# 07_-_ETHERNET.net
KiCad netlist of a schematic drawn in Altium Designer
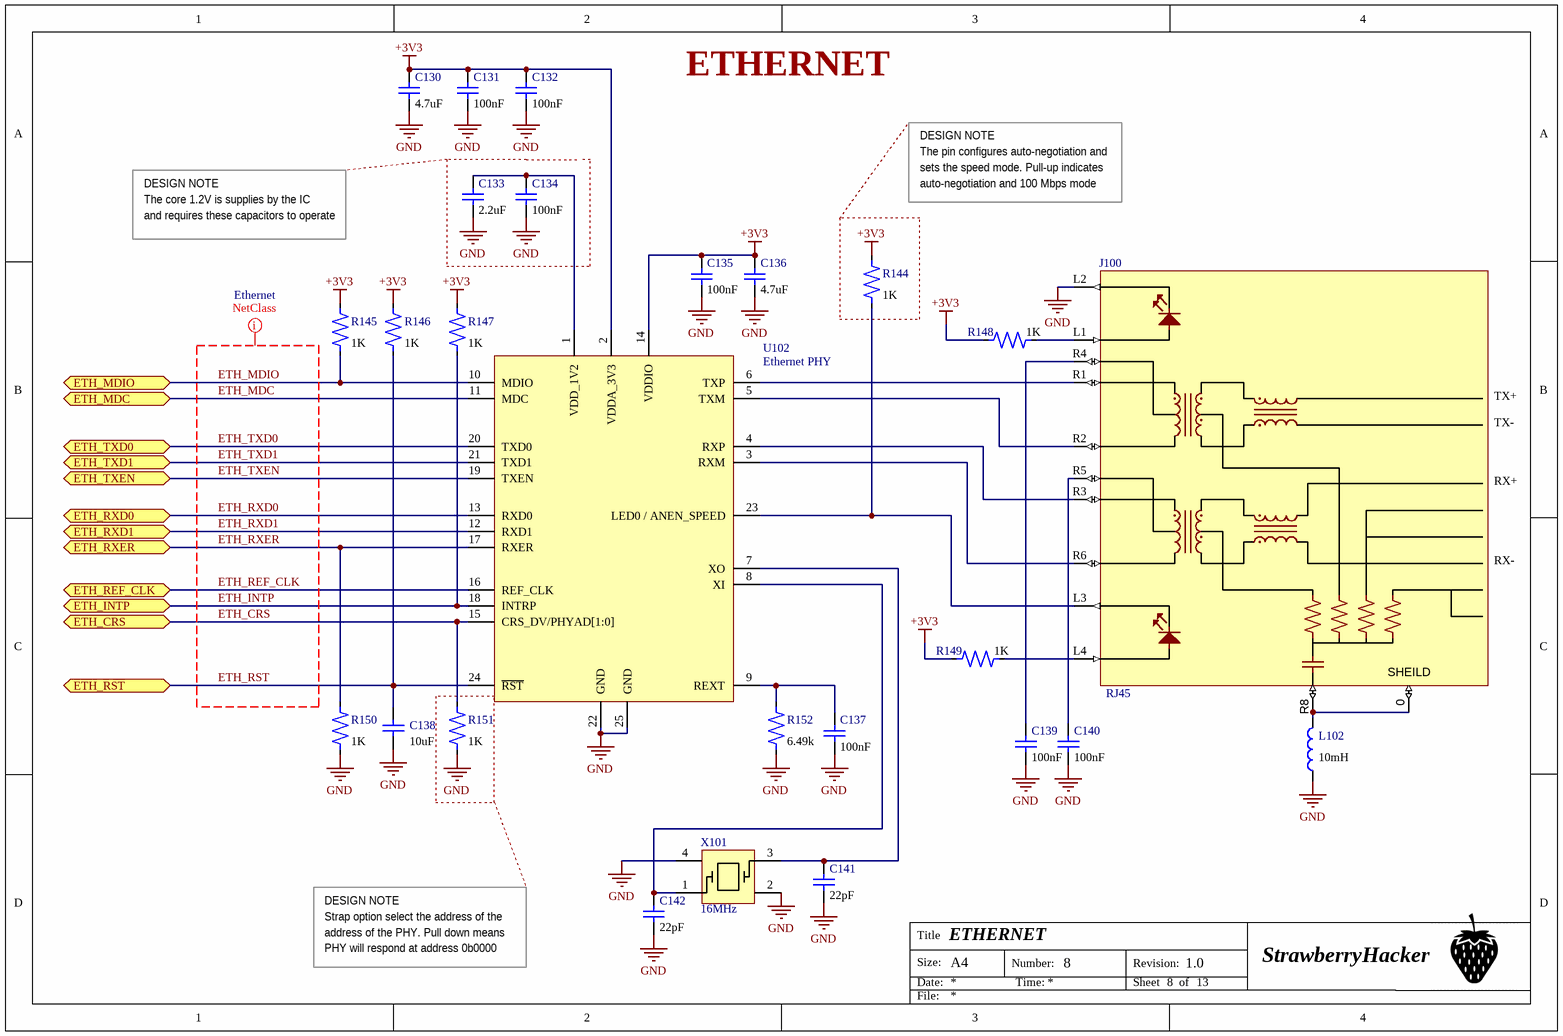
[diagram p0: [07] - ETHERNET.SchDoc]

(export (version "E")
  (design (tool "Eeschema 10.0.6"))
  (components
    (comp (ref "C130")
      (value "4.7uF")
      (footprint "C0603")
      (description "C0603")
      (fields (field (name "Comment") "02016D104KAT2A"))
      (libsource (lib "Passive components") (part "02016D104KAT2A"))
    )
    (comp (ref "C131")
      (value "100nF")
      (footprint "C0402")
      (description "C0402")
      (fields (field (name "Comment") "04023C103KAT2A"))
      (libsource (lib "Passive components") (part "04023C103KAT2A"))
    )
    (comp (ref "C132")
      (value "100nF")
      (footprint "C0402")
      (description "C0402")
      (fields (field (name "Comment") "04023C103KAT2A"))
      (libsource (lib "Passive components") (part "04023C103KAT2A"))
    )
    (comp (ref "C133")
      (value "2.2uF")
      (footprint "C0603")
      (description "C0603")
      (fields (field (name "Comment") "02016D104KAT2A"))
      (libsource (lib "Passive components") (part "02016D104KAT2A"))
    )
    (comp (ref "C134")
      (value "100nF")
      (footprint "C0402")
      (description "C0402")
      (fields (field (name "Comment") "04023C103KAT2A"))
      (libsource (lib "Passive components") (part "04023C103KAT2A"))
    )
    (comp (ref "C135")
      (value "100nF")
      (footprint "C0402")
      (description "C0402")
      (fields (field (name "Comment") "04023C103KAT2A"))
      (libsource (lib "Passive components") (part "04023C103KAT2A"))
    )
    (comp (ref "C136")
      (value "4.7uF")
      (footprint "C0603")
      (description "C0603")
      (fields (field (name "Comment") "02016D104KAT2A"))
      (libsource (lib "Passive components") (part "02016D104KAT2A"))
    )
    (comp (ref "C137")
      (value "100nF")
      (footprint "C0402")
      (description "C0402")
      (fields (field (name "Comment") "04023C103KAT2A"))
      (libsource (lib "Passive components") (part "04023C103KAT2A"))
    )
    (comp (ref "C138")
      (value "10uF")
      (footprint "C0603")
      (description "C0603")
      (fields (field (name "Comment") "02016D104KAT2A"))
      (libsource (lib "Passive components") (part "02016D104KAT2A"))
    )
    (comp (ref "C139")
      (value "100nF")
      (footprint "C0402")
      (description "C0402")
      (fields (field (name "Comment") "04023C103KAT2A"))
      (libsource (lib "Passive components") (part "04023C103KAT2A"))
    )
    (comp (ref "C140")
      (value "100nF")
      (footprint "C0402")
      (description "C0402")
      (fields (field (name "Comment") "04023C103KAT2A"))
      (libsource (lib "Passive components") (part "04023C103KAT2A"))
    )
    (comp (ref "C141")
      (value "22pF")
      (footprint "C0402")
      (description "C0402")
      (fields (field (name "Comment") "04023C103KAT2A"))
      (libsource (lib "Passive components") (part "04023C103KAT2A"))
    )
    (comp (ref "C142")
      (value "22pF")
      (footprint "C0402")
      (description "C0402")
      (fields (field (name "Comment") "04023C103KAT2A"))
      (libsource (lib "Passive components") (part "04023C103KAT2A"))
    )
    (comp (ref "J100")
      (value "RJ45")
      (footprint "RJ45 8P8C LED & magnetics")
      (description "RJ45 8P8C LED & magnetics")
      (libsource (lib "Connectors") (part "234235-2-2-1-12"))
    )
    (comp (ref "L102")
      (value "10mH")
      (footprint "Inductor 0603")
      (description "Inductor 0603")
      (fields (field (name "Comment") "MLZ1608A2R2WT"))
      (libsource (lib "Passive components") (part "MLZ1608A2R2WT"))
    )
    (comp (ref "R144")
      (value "1K")
      (footprint "R0402")
      (description "R0402")
      (fields (field (name "Comment") "CRCW04020000Z0ED"))
      (libsource (lib "Passive components") (part "CRCW04020000Z0ED"))
    )
    (comp (ref "R145")
      (value "1K")
      (footprint "R0402")
      (description "R0402")
      (fields (field (name "Comment") "CRCW04020000Z0ED"))
      (libsource (lib "Passive components") (part "CRCW04020000Z0ED"))
    )
    (comp (ref "R146")
      (value "1K")
      (footprint "R0402")
      (description "R0402")
      (fields (field (name "Comment") "CRCW04020000Z0ED"))
      (libsource (lib "Passive components") (part "CRCW04020000Z0ED"))
    )
    (comp (ref "R147")
      (value "1K")
      (footprint "R0402")
      (description "R0402")
      (fields (field (name "Comment") "CRCW04020000Z0ED"))
      (libsource (lib "Passive components") (part "CRCW04020000Z0ED"))
    )
    (comp (ref "R148")
      (value "1K")
      (footprint "R0402")
      (description "R0402")
      (fields (field (name "Comment") "CRCW04020000Z0ED"))
      (libsource (lib "Passive components") (part "CRCW04020000Z0ED"))
    )
    (comp (ref "R149")
      (value "1K")
      (footprint "R0402")
      (description "R0402")
      (fields (field (name "Comment") "CRCW04020000Z0ED"))
      (libsource (lib "Passive components") (part "CRCW04020000Z0ED"))
    )
    (comp (ref "R150")
      (value "1K")
      (footprint "R0402")
      (description "R0402")
      (fields (field (name "Comment") "CRCW04020000Z0ED"))
      (libsource (lib "Passive components") (part "CRCW04020000Z0ED"))
    )
    (comp (ref "R151")
      (value "1K")
      (footprint "R0402")
      (description "R0402")
      (fields (field (name "Comment") "CRCW04020000Z0ED"))
      (libsource (lib "Passive components") (part "CRCW04020000Z0ED"))
    )
    (comp (ref "R152")
      (value "6.49k")
      (footprint "R0402")
      (description "R0402")
      (fields (field (name "Comment") "CRCW04020000Z0ED"))
      (libsource (lib "Passive components") (part "CRCW04020000Z0ED"))
    )
    (comp (ref "U102")
      (value "Ethernet PHY")
      (footprint "KSZ8081RNACA")
      (description "Ethernet PHY 10BASE-T/100BASE")
      (libsource (lib "IC") (part "KSZ8081RNACA"))
    )
    (comp (ref "X101")
      (value "16MHz")
      (footprint "MCSJK-7U-16.00-12-10-80-B-10")
      (description "Crystal 25MHx 3.2mm x 2.5mm, 16pF")
      (libsource (lib "Crystals") (part "MCSJK-7U-16.00-12-10-80-B-10_1"))
    )
  )
  (nets
    (net (code "1") (name "+3V3") (class "Default")
      (node (ref "C130") (pin "2") (pinfunction "2_2") (pintype "passive"))
      (node (ref "C131") (pin "2") (pinfunction "2_2") (pintype "passive"))
      (node (ref "C132") (pin "2") (pinfunction "2_2") (pintype "passive"))
      (node (ref "C135") (pin "2") (pinfunction "2_2") (pintype "passive"))
      (node (ref "C136") (pin "2") (pinfunction "2_2") (pintype "passive"))
      (node (ref "R144") (pin "2") (pinfunction "3_2") (pintype "passive"))
      (node (ref "R145") (pin "2") (pinfunction "3_2") (pintype "passive"))
      (node (ref "R146") (pin "2") (pinfunction "3_2") (pintype "passive"))
      (node (ref "R147") (pin "2") (pinfunction "3_2") (pintype "passive"))
      (node (ref "R148") (pin "1") (pinfunction "1_1") (pintype "passive"))
      (node (ref "R149") (pin "1") (pinfunction "1_1") (pintype "passive"))
      (node (ref "U102") (pin "14") (pinfunction "VDDIO_14") (pintype "passive"))
      (node (ref "U102") (pin "2") (pinfunction "VDDA_3V3_2") (pintype "passive"))
    )
    (net (code "2") (name "/ETH_CRS") (class "Default")
      (node (ref "R151") (pin "2") (pinfunction "3_2") (pintype "passive"))
      (node (ref "U102") (pin "15") (pinfunction "CRS_DV/PHYAD[1:0]_15") (pintype "passive"))
    )
    (net (code "3") (name "/ETH_INTP") (class "Default")
      (node (ref "R147") (pin "1") (pinfunction "1_1") (pintype "passive"))
      (node (ref "U102") (pin "18") (pinfunction "INTRP_18") (pintype "passive"))
    )
    (net (code "4") (name "/ETH_MDC") (class "Default")
      (node (ref "U102") (pin "11") (pinfunction "MDC_11") (pintype "passive"))
    )
    (net (code "5") (name "/ETH_MDIO") (class "Default")
      (node (ref "R145") (pin "1") (pinfunction "1_1") (pintype "passive"))
      (node (ref "U102") (pin "10") (pinfunction "MDIO_10") (pintype "passive"))
    )
    (net (code "6") (name "/ETH_REF_CLK") (class "Default")
      (node (ref "U102") (pin "16") (pinfunction "REF_CLK_16") (pintype "passive"))
    )
    (net (code "7") (name "/ETH_RST") (class "Default")
      (node (ref "C138") (pin "2") (pinfunction "2_2") (pintype "passive"))
      (node (ref "R146") (pin "1") (pinfunction "1_1") (pintype "passive"))
      (node (ref "U102") (pin "24") (pinfunction "~{RST}_24") (pintype "passive"))
    )
    (net (code "8") (name "/ETH_RXD0") (class "Default")
      (node (ref "U102") (pin "13") (pinfunction "RXD0_13") (pintype "passive"))
    )
    (net (code "9") (name "/ETH_RXD1") (class "Default")
      (node (ref "U102") (pin "12") (pinfunction "RXD1_12") (pintype "passive"))
    )
    (net (code "10") (name "/ETH_RXER") (class "Default")
      (node (ref "R150") (pin "2") (pinfunction "3_2") (pintype "passive"))
      (node (ref "U102") (pin "17") (pinfunction "RXER_17") (pintype "passive"))
    )
    (net (code "11") (name "/ETH_TXD0") (class "Default")
      (node (ref "U102") (pin "20") (pinfunction "TXD0_20") (pintype "passive"))
    )
    (net (code "12") (name "/ETH_TXD1") (class "Default")
      (node (ref "U102") (pin "21") (pinfunction "TXD1_21") (pintype "passive"))
    )
    (net (code "13") (name "/ETH_TXEN") (class "Default")
      (node (ref "U102") (pin "19") (pinfunction "TXEN_19") (pintype "passive"))
    )
    (net (code "14") (name "GND") (class "Default")
      (node (ref "C130") (pin "1") (pinfunction "1_1") (pintype "passive"))
      (node (ref "C131") (pin "1") (pinfunction "1_1") (pintype "passive"))
      (node (ref "C132") (pin "1") (pinfunction "1_1") (pintype "passive"))
      (node (ref "C133") (pin "1") (pinfunction "1_1") (pintype "passive"))
      (node (ref "C134") (pin "1") (pinfunction "1_1") (pintype "passive"))
      (node (ref "C135") (pin "1") (pinfunction "1_1") (pintype "passive"))
      (node (ref "C136") (pin "1") (pinfunction "1_1") (pintype "passive"))
      (node (ref "C137") (pin "1") (pinfunction "1_1") (pintype "passive"))
      (node (ref "C138") (pin "1") (pinfunction "1_1") (pintype "passive"))
      (node (ref "C139") (pin "1") (pinfunction "1_1") (pintype "passive"))
      (node (ref "C140") (pin "1") (pinfunction "1_1") (pintype "passive"))
      (node (ref "C141") (pin "1") (pinfunction "1_1") (pintype "passive"))
      (node (ref "C142") (pin "1") (pinfunction "1_1") (pintype "passive"))
      (node (ref "J100") (pin "L2") (pintype "output"))
      (node (ref "L102") (pin "1") (pinfunction "1_1") (pintype "passive"))
      (node (ref "R150") (pin "1") (pinfunction "1_1") (pintype "passive"))
      (node (ref "R151") (pin "1") (pinfunction "1_1") (pintype "passive"))
      (node (ref "R152") (pin "1") (pinfunction "1_1") (pintype "passive"))
      (node (ref "U102") (pin "22") (pinfunction "GND_22") (pintype "passive"))
      (node (ref "U102") (pin "25") (pinfunction "GND_25") (pintype "passive"))
      (node (ref "X101") (pin "2") (pinfunction "2_2") (pintype "passive"))
      (node (ref "X101") (pin "4") (pinfunction "4_4") (pintype "passive"))
    )
    (net (code "15") (name "Net-(C139-Pad2)") (class "Default")
      (node (ref "C139") (pin "2") (pinfunction "2_2") (pintype "passive"))
      (node (ref "J100") (pin "R4") (pintype "bidirectional"))
    )
    (net (code "16") (name "Net-(C140-Pad2)") (class "Default")
      (node (ref "C140") (pin "2") (pinfunction "2_2") (pintype "passive"))
      (node (ref "J100") (pin "R5") (pintype "bidirectional"))
    )
    (net (code "17") (name "Net-(J100-Pad0)") (class "Default")
      (node (ref "J100") (pin "0") (pintype "bidirectional"))
      (node (ref "J100") (pin "R8") (pintype "bidirectional"))
      (node (ref "L102") (pin "2") (pinfunction "2_2") (pintype "passive"))
    )
    (net (code "18") (name "Net-(R148-3)") (class "Default")
      (node (ref "J100") (pin "L1") (pintype "input"))
      (node (ref "R148") (pin "2") (pinfunction "3_2") (pintype "passive"))
    )
    (net (code "19") (name "Net-(R149-3)") (class "Default")
      (node (ref "J100") (pin "L4") (pintype "input"))
      (node (ref "R149") (pin "2") (pinfunction "3_2") (pintype "passive"))
    )
    (net (code "20") (name "Net-(R152-3)") (class "Default")
      (node (ref "C137") (pin "2") (pinfunction "2_2") (pintype "passive"))
      (node (ref "R152") (pin "2") (pinfunction "3_2") (pintype "passive"))
      (node (ref "U102") (pin "9") (pinfunction "REXT_9") (pintype "passive"))
    )
    (net (code "21") (name "Net-(U102-LED0_{slash}_ANEN_SPEED)") (class "Default")
      (node (ref "J100") (pin "L3") (pintype "output"))
      (node (ref "R144") (pin "1") (pinfunction "1_1") (pintype "passive"))
      (node (ref "U102") (pin "23") (pinfunction "LED0_/_ANEN_SPEED_23") (pintype "passive"))
    )
    (net (code "22") (name "Net-(U102-RXM)") (class "Default")
      (node (ref "J100") (pin "R6") (pintype "bidirectional"))
      (node (ref "U102") (pin "3") (pinfunction "RXM_3") (pintype "passive"))
    )
    (net (code "23") (name "Net-(U102-RXP)") (class "Default")
      (node (ref "J100") (pin "R3") (pintype "bidirectional"))
      (node (ref "U102") (pin "4") (pinfunction "RXP_4") (pintype "passive"))
    )
    (net (code "24") (name "Net-(U102-TXM)") (class "Default")
      (node (ref "J100") (pin "R2") (pintype "bidirectional"))
      (node (ref "U102") (pin "5") (pinfunction "TXM_5") (pintype "passive"))
    )
    (net (code "25") (name "Net-(U102-TXP)") (class "Default")
      (node (ref "J100") (pin "R1") (pintype "bidirectional"))
      (node (ref "U102") (pin "6") (pinfunction "TXP_6") (pintype "passive"))
    )
    (net (code "26") (name "Net-(U102-VDD_1V2)") (class "Default")
      (node (ref "C133") (pin "2") (pinfunction "2_2") (pintype "passive"))
      (node (ref "C134") (pin "2") (pinfunction "2_2") (pintype "passive"))
      (node (ref "U102") (pin "1") (pinfunction "VDD_1V2_1") (pintype "passive"))
    )
    (net (code "27") (name "Net-(U102-XI)") (class "Default")
      (node (ref "C142") (pin "2") (pinfunction "2_2") (pintype "passive"))
      (node (ref "U102") (pin "8") (pinfunction "XI_8") (pintype "passive"))
      (node (ref "X101") (pin "1") (pinfunction "2_1") (pintype "passive"))
    )
    (net (code "28") (name "Net-(U102-XO)") (class "Default")
      (node (ref "C141") (pin "2") (pinfunction "2_2") (pintype "passive"))
      (node (ref "U102") (pin "7") (pinfunction "XO_7") (pintype "passive"))
      (node (ref "X101") (pin "3") (pinfunction "2_3") (pintype "passive"))
    )
    (net (code "29") (name "unconnected-(J100-Pad1)") (class "Default")
      (node (ref "J100") (pin "1") (pinfunction "1_1") (pintype "passive"))
    )
    (net (code "30") (name "unconnected-(J100-Pad1)_1") (class "Default")
      (node (ref "J100") (pin "1") (pinfunction "1_1") (pintype "passive"))
    )
    (net (code "31") (name "unconnected-(J100-Pad2)") (class "Default")
      (node (ref "J100") (pin "2") (pinfunction "2_2") (pintype "passive"))
    )
    (net (code "32") (name "unconnected-(J100-Pad2)_1") (class "Default")
      (node (ref "J100") (pin "2") (pinfunction "2_2") (pintype "passive"))
    )
  )
)
